# design.net
KiCad netlist of a schematic drawn in EasyEDA Pro
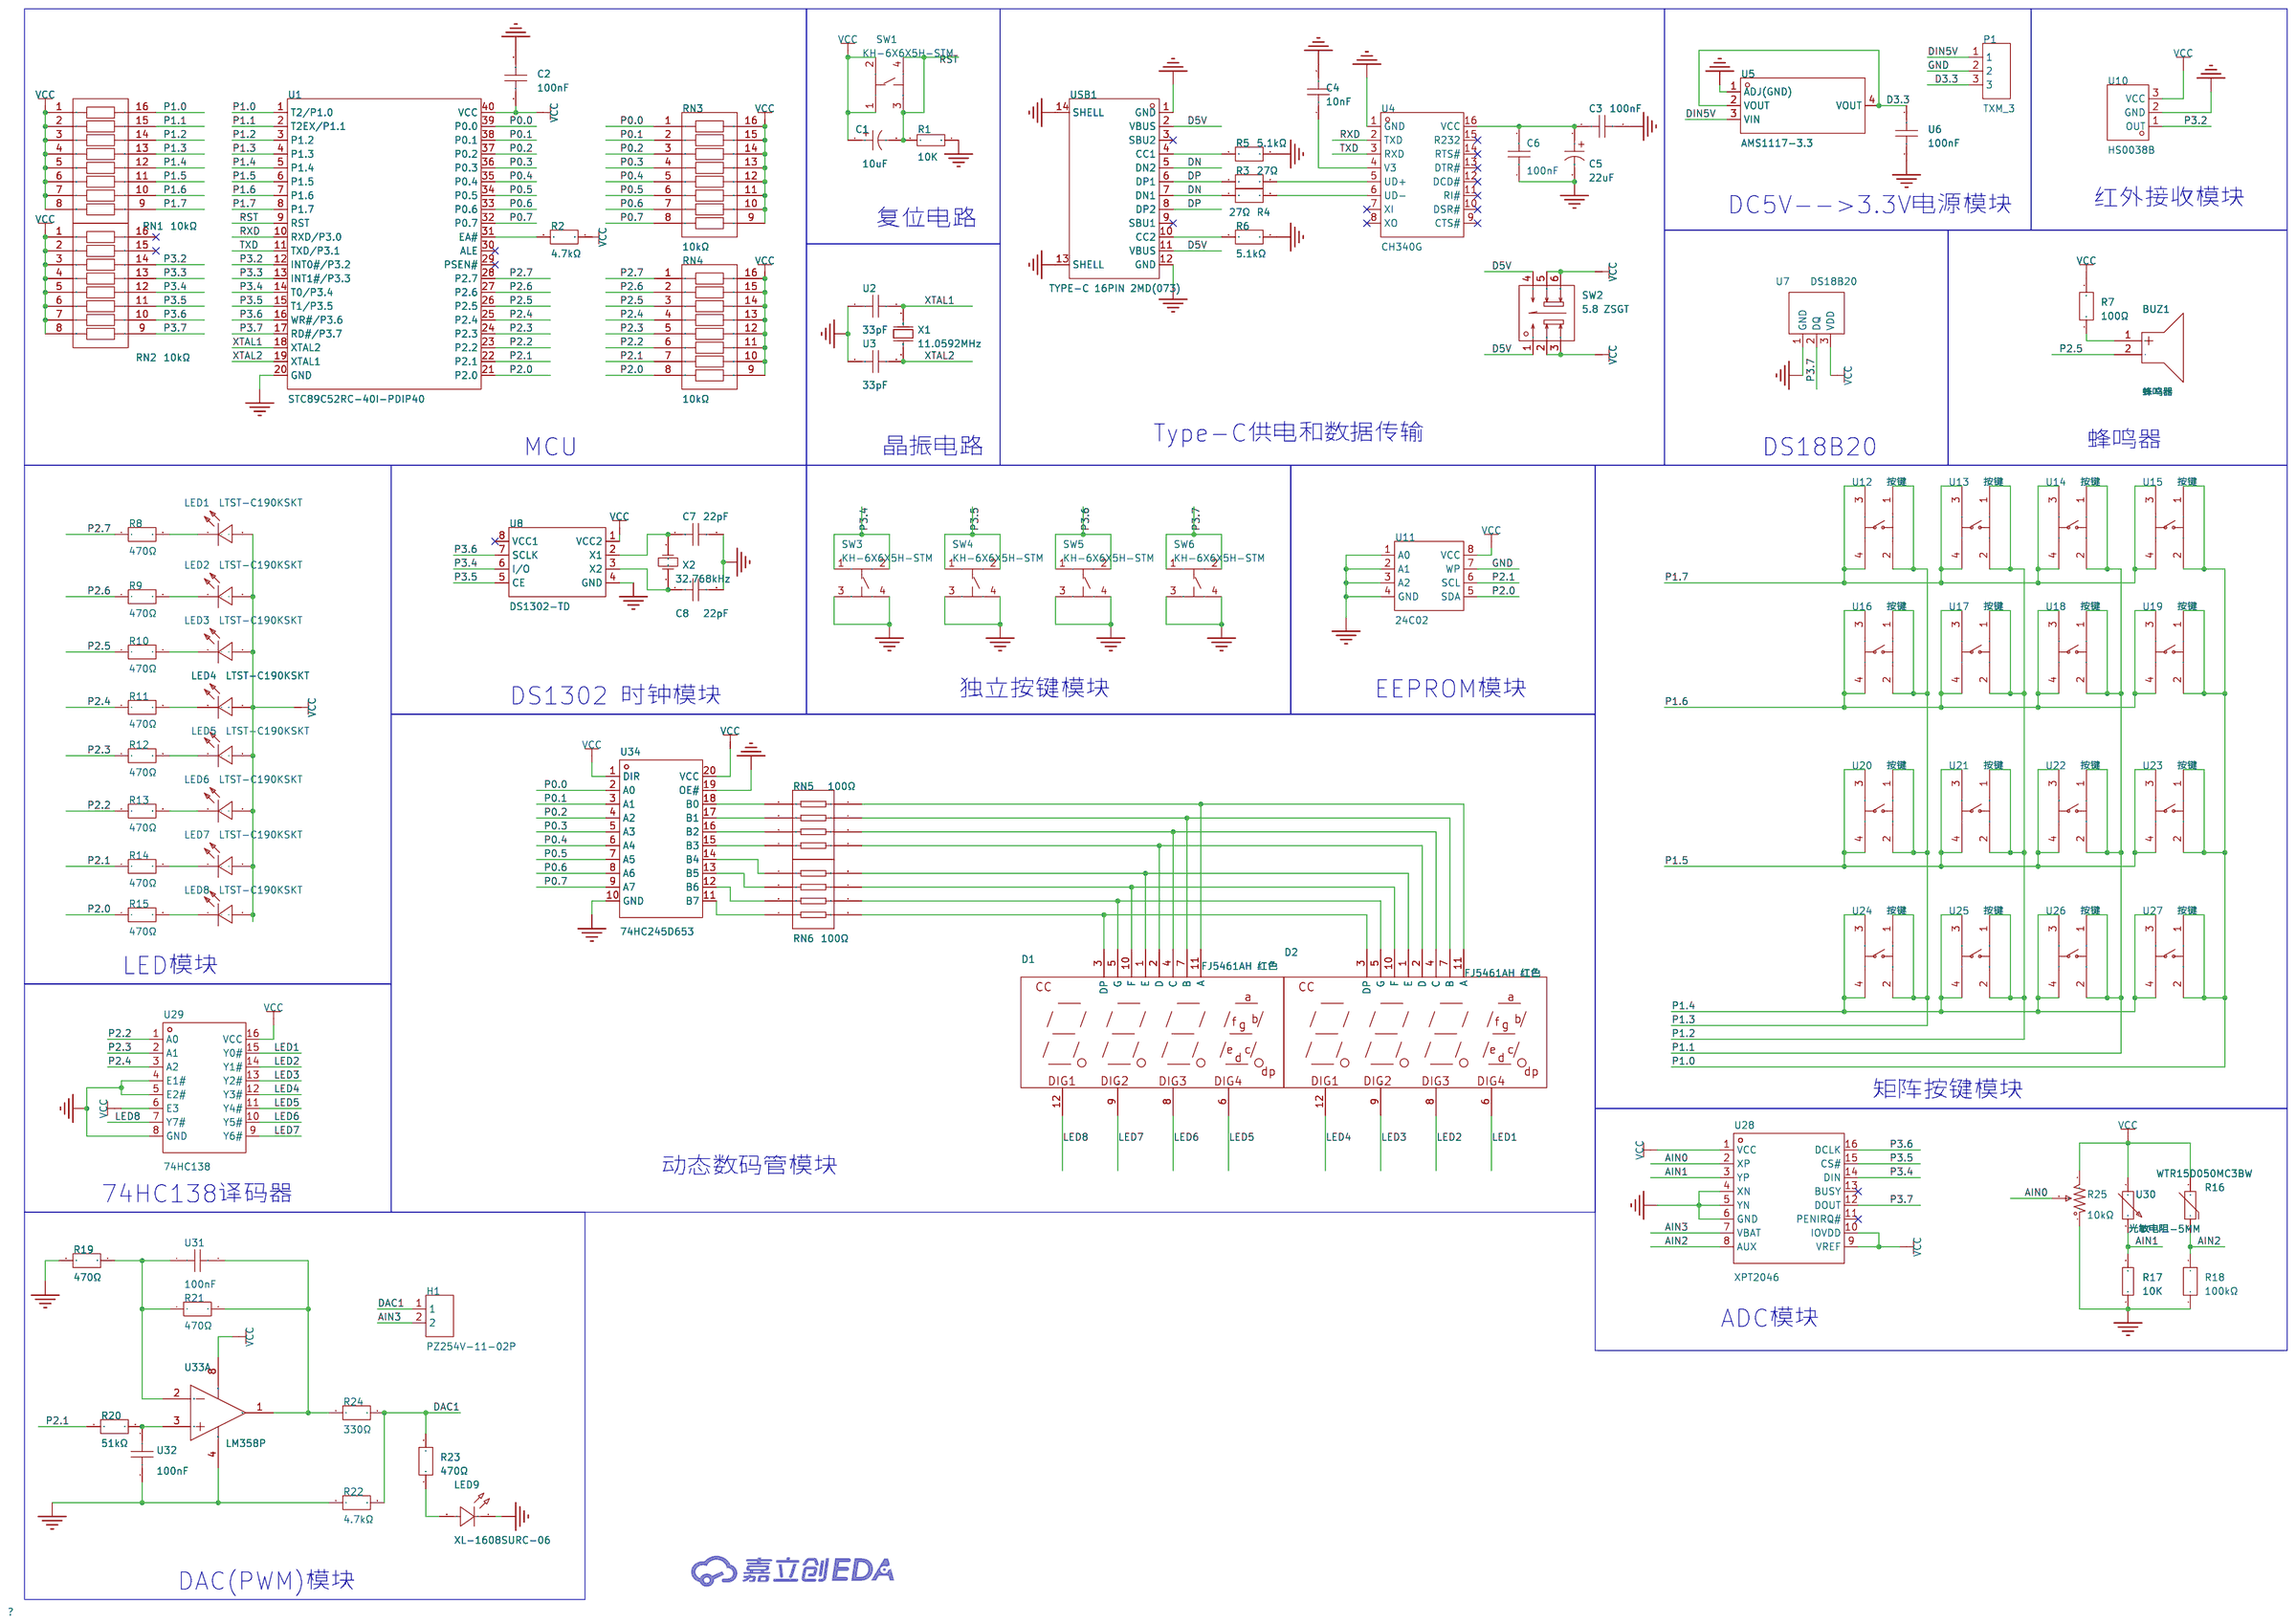
[diagram p0: schematic sheet]

(export (version "E")
  (design (tool "Eeschema 10.0.6"))
  (components
    (comp (ref "BUZ1")
      (value "蜂鸣器")
      (footprint "easyedapro:BUZ-TH_BD9.0-P5.00-D0.6-FD")
      (libsource (lib "easyedapro") (part "蜂鸣器"))
    )
    (comp (ref "C1")
      (value "10uF")
      (footprint "easyedapro:CAP-TH_BD10.0-P5.00-D0.6-FD_1")
      (description "容值:10uF;精度:±20%;额定电压:450V;纹波电流:200mA@100kHz;等效串联电阻(ESR):9Ω@100kHz;")
      (fields (field (name "Manufacturer Part") "CV100MPA16B") (field (name "Manufacturer") "TWBOR(伯鸿)"))
      (libsource (lib "easyedapro") (part "CV100MPA16B"))
    )
    (comp (ref "C2")
      (value "100nF")
      (footprint "easyedapro:C0603")
      (description "容值:100nF;精度:±10%;额定电压:25V;温度系数:X7R;")
      (fields
        (field (name "Manufacturer Part") "0603X7R104K250NT")
        (field (name "Manufacturer") "AIDE(爱迪电容)")
      )
      (libsource (lib "easyedapro") (part "0603X7R104K250NT"))
    )
    (comp (ref "C3")
      (value "100nF")
      (footprint "easyedapro:C0603")
      (description "容值:100nF;精度:±10%;额定电压:25V;温度系数:X7R;")
      (fields
        (field (name "Manufacturer Part") "0603X7R104K250NT")
        (field (name "Manufacturer") "AIDE(爱迪电容)")
      )
      (libsource (lib "easyedapro") (part "0603X7R104K250NT"))
    )
    (comp (ref "C4")
      (value "10nF")
      (footprint "easyedapro:C0603")
      (description "容值:10nF;精度:±10%;额定电压:200V;温度系数:X7R;")
      (fields
        (field (name "Manufacturer Part") "C0603X103K2RECAUTO")
        (field (name "Manufacturer") "KEMET(基美)")
      )
      (libsource (lib "easyedapro") (part "C0603X103K2RECAUTO"))
    )
    (comp (ref "C5")
      (value "22uF")
      (footprint "easyedapro:CAP-SMD_BD5.0-L5.3-W5.3-LS6.0-FD-H5.7")
      (description "容值:22uF;精度:±20%;额定电压:35V;纹波电流:95mA@120Hz;等效串联电阻(ESR):1.8Ω;")
      (fields (field (name "Manufacturer Part") "JVE35V22M5X6") (field (name "Manufacturer") "捷而瑞"))
      (libsource (lib "easyedapro") (part "JVE35V22M5X6"))
    )
    (comp (ref "C6")
      (value "100nF")
      (footprint "easyedapro:C0603")
      (description "容值:100nF;精度:±10%;额定电压:25V;温度系数:X7R;")
      (fields
        (field (name "Manufacturer Part") "0603X7R104K250NT")
        (field (name "Manufacturer") "AIDE(爱迪电容)")
      )
      (libsource (lib "easyedapro") (part "0603X7R104K250NT"))
    )
    (comp (ref "C7")
      (value "22pF")
      (footprint "easyedapro:C0603")
      (description "容值:22pF;精度:±10%;额定电压:16V;温度系数:C0G;")
      (fields
        (field (name "Manufacturer Part") "C0603C220K4GACAUTO")
        (field (name "Manufacturer") "KEMET(基美)")
      )
      (libsource (lib "easyedapro") (part "C0603C220K4GACAUTO"))
    )
    (comp (ref "C8")
      (value "22pF")
      (footprint "easyedapro:C0603")
      (description "容值:22pF;精度:±10%;额定电压:16V;温度系数:C0G;")
      (fields
        (field (name "Manufacturer Part") "C0603C220K4GACAUTO")
        (field (name "Manufacturer") "KEMET(基美)")
      )
      (libsource (lib "easyedapro") (part "C0603C220K4GACAUTO"))
    )
    (comp (ref "D1")
      (value "FJ5461AH 红色")
      (footprint "easyedapro:LED-SEG-TH_FJ5461AH")
      (description "数码管位数:4位;功耗:-;发光颜色:红色;LED极性:共阴极;数字/字母大小(英寸):0.56;")
      (fields (field (name "Manufacturer") "志浩"))
      (libsource (lib "easyedapro") (part "FJ5461AH red"))
    )
    (comp (ref "D2")
      (value "FJ5461AH 红色")
      (footprint "easyedapro:LED-SEG-TH_FJ5461AH")
      (description "数码管位数:4位;功耗:-;发光颜色:红色;LED极性:共阴极;数字/字母大小(英寸):0.56;")
      (fields (field (name "Manufacturer") "志浩"))
      (libsource (lib "easyedapro") (part "FJ5461AH red"))
    )
    (comp (ref "H1")
      (value "PZ254V-11-02P")
      (footprint "easyedapro:HDR-TH_2P-P2.54-V-M")
      (fields (field (name "Manufacturer") "XFCN(兴飞)"))
      (libsource (lib "easyedapro") (part "PZ254V-11-02P"))
    )
    (comp (ref "LED1")
      (value "LTST-C190KSKT")
      (footprint "easyedapro:LED0603-RD")
      (fields (field (name "Manufacturer") "LITEON(光宝)"))
      (libsource (lib "easyedapro") (part "LTST-C190KSKT"))
    )
    (comp (ref "LED2")
      (value "LTST-C190KSKT")
      (footprint "easyedapro:LED0603-RD")
      (fields (field (name "Manufacturer") "LITEON(光宝)"))
      (libsource (lib "easyedapro") (part "LTST-C190KSKT"))
    )
    (comp (ref "LED3")
      (value "LTST-C190KSKT")
      (footprint "easyedapro:LED0603-RD")
      (fields (field (name "Manufacturer") "LITEON(光宝)"))
      (libsource (lib "easyedapro") (part "LTST-C190KSKT"))
    )
    (comp (ref "LED4")
      (value "LTST-C190KSKT")
      (footprint "easyedapro:LED0603-RD")
      (fields (field (name "Manufacturer") "LITEON(光宝)"))
      (libsource (lib "easyedapro") (part "LTST-C190KSKT"))
    )
    (comp (ref "LED5")
      (value "LTST-C190KSKT")
      (footprint "easyedapro:LED0603-RD")
      (fields (field (name "Manufacturer") "LITEON(光宝)"))
      (libsource (lib "easyedapro") (part "LTST-C190KSKT"))
    )
    (comp (ref "LED6")
      (value "LTST-C190KSKT")
      (footprint "easyedapro:LED0603-RD")
      (fields (field (name "Manufacturer") "LITEON(光宝)"))
      (libsource (lib "easyedapro") (part "LTST-C190KSKT"))
    )
    (comp (ref "LED7")
      (value "LTST-C190KSKT")
      (footprint "easyedapro:LED0603-RD")
      (fields (field (name "Manufacturer") "LITEON(光宝)"))
      (libsource (lib "easyedapro") (part "LTST-C190KSKT"))
    )
    (comp (ref "LED8")
      (value "LTST-C190KSKT")
      (footprint "easyedapro:LED0603-RD")
      (fields (field (name "Manufacturer") "LITEON(光宝)"))
      (libsource (lib "easyedapro") (part "LTST-C190KSKT"))
    )
    (comp (ref "LED9")
      (value "XL-1608SURC-06")
      (footprint "easyedapro:LED0603-RD_RED")
      (fields (field (name "Manufacturer") "XINGLIGHT(成兴光)"))
      (libsource (lib "easyedapro") (part "XL-1608SURC-06"))
    )
    (comp (ref "P1")
      (value "TXM_3")
      (footprint "easyedapro:HDR-TH_3P-P2.54-V-M-A")
      (libsource (lib "easyedapro") (part "TXM_3"))
    )
    (comp (ref "R1") (value "10K") (footprint "easyedapro:R0603") (libsource (lib "easyedapro") (part "电阻")))
    (comp (ref "R2")
      (value "4.7kΩ")
      (footprint "easyedapro:R0805")
      (description "电阻类型:厚膜电阻;阻值:4.7kΩ;精度:±1%;功率:125mW;工作电压:-;温度系数:±100ppm/°C;")
      (fields
        (field (name "Manufacturer Part") "ERJ-U06F4701V")
        (field (name "Manufacturer") "PANASONIC(松下)")
      )
      (libsource (lib "easyedapro") (part "ERJ-U06F4701V"))
    )
    (comp (ref "R3")
      (value "27Ω")
      (footprint "easyedapro:R0805")
      (description "电阻类型:厚膜电阻;阻值:27Ω;精度:±5%;功率:125mW;工作电压:150V;温度系数:±100ppm/°C;")
      (fields (field (name "Manufacturer Part") "FRC0805J270 TS") (field (name "Manufacturer") "FOJAN(富捷)"))
      (libsource (lib "easyedapro") (part "FRC0805J270 TS"))
    )
    (comp (ref "R4")
      (value "27Ω")
      (footprint "easyedapro:R0805")
      (description "电阻类型:厚膜电阻;阻值:27Ω;精度:±5%;功率:125mW;工作电压:150V;温度系数:±100ppm/°C;")
      (fields (field (name "Manufacturer Part") "FRC0805J270 TS") (field (name "Manufacturer") "FOJAN(富捷)"))
      (libsource (lib "easyedapro") (part "FRC0805J270 TS"))
    )
    (comp (ref "R5")
      (value "5.1kΩ")
      (footprint "easyedapro:R0603")
      (description "电阻类型:薄膜电阻;阻值:5.1kΩ;精度:±0.01%;功率:100mW;温度系数:±2ppm/°C;")
      (fields
        (field (name "Manufacturer Part") "RNCF0603TKW5K10")
        (field (name "Manufacturer") "SEI(Stackpole Electronics Inc.)")
      )
      (libsource (lib "easyedapro") (part "RNCF0603TKW5K10"))
    )
    (comp (ref "R6")
      (value "5.1kΩ")
      (footprint "easyedapro:R0603")
      (description "电阻类型:薄膜电阻;阻值:5.1kΩ;精度:±0.01%;功率:100mW;温度系数:±2ppm/°C;")
      (fields
        (field (name "Manufacturer Part") "RNCF0603TKW5K10")
        (field (name "Manufacturer") "SEI(Stackpole Electronics Inc.)")
      )
      (libsource (lib "easyedapro") (part "RNCF0603TKW5K10"))
    )
    (comp (ref "R7")
      (value "100Ω")
      (footprint "easyedapro:R1206")
      (description "电阻类型:-;阻值:100Ω;精度:±5%;功率:250mW;工作电压:200V;")
      (fields
        (field (name "Manufacturer Part") "CQ06W4J0101T5E")
        (field (name "Manufacturer") "UNI-ROYAL(厚声)")
      )
      (libsource (lib "easyedapro") (part "CQ06W4J0101T5E"))
    )
    (comp (ref "R8")
      (value "470Ω")
      (footprint "easyedapro:R0402")
      (description "电阻类型:厚膜电阻;阻值:470Ω;精度:±1%;功率:62.5mW;工作电压:50V;温度系数:±100ppm/°C;")
      (fields (field (name "Manufacturer Part") "FRC0402F4700TS") (field (name "Manufacturer") "FOJAN(富捷)"))
      (libsource (lib "easyedapro") (part "FRC0402F4700TS"))
    )
    (comp (ref "R9")
      (value "470Ω")
      (footprint "easyedapro:R0402")
      (description "电阻类型:厚膜电阻;阻值:470Ω;精度:±1%;功率:62.5mW;工作电压:50V;温度系数:±100ppm/°C;")
      (fields (field (name "Manufacturer Part") "FRC0402F4700TS") (field (name "Manufacturer") "FOJAN(富捷)"))
      (libsource (lib "easyedapro") (part "FRC0402F4700TS"))
    )
    (comp (ref "R10")
      (value "470Ω")
      (footprint "easyedapro:R0402")
      (description "电阻类型:厚膜电阻;阻值:470Ω;精度:±1%;功率:62.5mW;工作电压:50V;温度系数:±100ppm/°C;")
      (fields (field (name "Manufacturer Part") "FRC0402F4700TS") (field (name "Manufacturer") "FOJAN(富捷)"))
      (libsource (lib "easyedapro") (part "FRC0402F4700TS"))
    )
    (comp (ref "R11")
      (value "470Ω")
      (footprint "easyedapro:R0402")
      (description "电阻类型:厚膜电阻;阻值:470Ω;精度:±1%;功率:62.5mW;工作电压:50V;温度系数:±100ppm/°C;")
      (fields (field (name "Manufacturer Part") "FRC0402F4700TS") (field (name "Manufacturer") "FOJAN(富捷)"))
      (libsource (lib "easyedapro") (part "FRC0402F4700TS"))
    )
    (comp (ref "R12")
      (value "470Ω")
      (footprint "easyedapro:R0402")
      (description "电阻类型:厚膜电阻;阻值:470Ω;精度:±1%;功率:62.5mW;工作电压:50V;温度系数:±100ppm/°C;")
      (fields (field (name "Manufacturer Part") "FRC0402F4700TS") (field (name "Manufacturer") "FOJAN(富捷)"))
      (libsource (lib "easyedapro") (part "FRC0402F4700TS"))
    )
    (comp (ref "R13")
      (value "470Ω")
      (footprint "easyedapro:R0402")
      (description "电阻类型:厚膜电阻;阻值:470Ω;精度:±1%;功率:62.5mW;工作电压:50V;温度系数:±100ppm/°C;")
      (fields (field (name "Manufacturer Part") "FRC0402F4700TS") (field (name "Manufacturer") "FOJAN(富捷)"))
      (libsource (lib "easyedapro") (part "FRC0402F4700TS"))
    )
    (comp (ref "R14")
      (value "470Ω")
      (footprint "easyedapro:R0402")
      (description "电阻类型:厚膜电阻;阻值:470Ω;精度:±1%;功率:62.5mW;工作电压:50V;温度系数:±100ppm/°C;")
      (fields (field (name "Manufacturer Part") "FRC0402F4700TS") (field (name "Manufacturer") "FOJAN(富捷)"))
      (libsource (lib "easyedapro") (part "FRC0402F4700TS"))
    )
    (comp (ref "R15")
      (value "470Ω")
      (footprint "easyedapro:R0402")
      (description "电阻类型:厚膜电阻;阻值:470Ω;精度:±1%;功率:62.5mW;工作电压:50V;温度系数:±100ppm/°C;")
      (fields (field (name "Manufacturer Part") "FRC0402F4700TS") (field (name "Manufacturer") "FOJAN(富捷)"))
      (libsource (lib "easyedapro") (part "FRC0402F4700TS"))
    )
    (comp (ref "R16")
      (value "WTR15D050MC3BW")
      (footprint "easyedapro:RES-TH_L17.5-W6.0-P7.50-D0.8-S5.20")
      (description "阻值(25°C):-;电阻精度:-;最大工作电压:-;功率:-;")
      (fields (field (name "Manufacturer") "WMEC(万明)"))
      (libsource (lib "easyedapro") (part "WTR15D050MC3BW"))
    )
    (comp (ref "R17") (value "10K") (footprint "easyedapro:R0603") (libsource (lib "easyedapro") (part "电阻")))
    (comp (ref "R18")
      (value "100kΩ")
      (footprint "easyedapro:R1206")
      (description "阻值:100kΩ;精度:±0.5%;")
      (fields (field (name "Manufacturer Part") "WF12R1003DTL") (field (name "Manufacturer") "Walsin(华新科)"))
      (libsource (lib "easyedapro") (part "WF12R1003DTL"))
    )
    (comp (ref "R19")
      (value "470Ω")
      (footprint "easyedapro:R0402")
      (description "电阻类型:厚膜电阻;阻值:470Ω;精度:±1%;功率:62.5mW;工作电压:50V;温度系数:±100ppm/°C;")
      (fields (field (name "Manufacturer Part") "FRC0402F4700TS") (field (name "Manufacturer") "FOJAN(富捷)"))
      (libsource (lib "easyedapro") (part "FRC0402F4700TS"))
    )
    (comp (ref "R20")
      (value "51kΩ")
      (footprint "easyedapro:R1812")
      (description "电阻类型:厚膜电阻;阻值:51kΩ;精度:±5%;功率:750mW;工作电压:200V;温度系数:±100ppm/°C;")
      (fields (field (name "Manufacturer Part") "FRC1812J513 TS") (field (name "Manufacturer") "FOJAN(富捷)"))
      (libsource (lib "easyedapro") (part "FRC1812J513 TS"))
    )
    (comp (ref "R21")
      (value "470Ω")
      (footprint "easyedapro:R0402")
      (description "电阻类型:厚膜电阻;阻值:470Ω;精度:±1%;功率:62.5mW;工作电压:50V;温度系数:±100ppm/°C;")
      (fields (field (name "Manufacturer Part") "FRC0402F4700TS") (field (name "Manufacturer") "FOJAN(富捷)"))
      (libsource (lib "easyedapro") (part "FRC0402F4700TS"))
    )
    (comp (ref "R22")
      (value "4.7kΩ")
      (footprint "easyedapro:R0603")
      (description "阻值:4.7kΩ;精度:±1%;功率:100mW;")
      (fields (field (name "Manufacturer Part") "RCA034K7FLF") (field (name "Manufacturer") "HKR(香港电阻)"))
      (libsource (lib "easyedapro") (part "RCA034K7FLF"))
    )
    (comp (ref "R23")
      (value "470Ω")
      (footprint "easyedapro:R0402")
      (description "电阻类型:厚膜电阻;阻值:470Ω;精度:±1%;功率:62.5mW;工作电压:50V;温度系数:±100ppm/°C;")
      (fields (field (name "Manufacturer Part") "FRC0402F4700TS") (field (name "Manufacturer") "FOJAN(富捷)"))
      (libsource (lib "easyedapro") (part "FRC0402F4700TS"))
    )
    (comp (ref "R24")
      (value "330Ω")
      (footprint "easyedapro:R2010")
      (description "电阻类型:厚膜电阻;阻值:330Ω;精度:±5%;功率:750mW;温度系数:±100ppm/°C;")
      (fields (field (name "Manufacturer Part") "AC2010JK-07330RL") (field (name "Manufacturer") "YAGEO(国巨)"))
      (libsource (lib "easyedapro") (part "AC2010JK-07330RL"))
    )
    (comp (ref "R25")
      (value "10kΩ")
      (footprint "easyedapro:RES-ADJ-SMD_RM065-V1")
      (description "阻值:10kΩ;精度:±25%;功率:100mW;")
      (fields (field (name "Manufacturer Part") "RM065-103(10K)") (field (name "Manufacturer") "BOCHEN(博晨)"))
      (libsource (lib "easyedapro") (part "RM065-103(10K)"))
    )
    (comp (ref "RN1")
      (value "10kΩ")
      (footprint "easyedapro:DIP-16_L22.0-W6.7-P2.54-LS7.6-BL")
      (description "电阻器数:8;阻值:10kΩ;精度:±2%;单个元件功率:250mW;温度系数:±100ppm/°C;")
      (fields (field (name "Manufacturer Part") "4116R-1-103LF") (field (name "Manufacturer") "BOURNS"))
      (libsource (lib "easyedapro") (part "4116R-1-103LF"))
    )
    (comp (ref "RN2")
      (value "10kΩ")
      (footprint "easyedapro:DIP-16_L22.0-W6.7-P2.54-LS7.6-BL")
      (description "电阻器数:8;阻值:10kΩ;精度:±2%;单个元件功率:250mW;温度系数:±100ppm/°C;")
      (fields (field (name "Manufacturer Part") "4116R-1-103LF") (field (name "Manufacturer") "BOURNS"))
      (libsource (lib "easyedapro") (part "4116R-1-103LF"))
    )
    (comp (ref "RN3")
      (value "10kΩ")
      (footprint "easyedapro:DIP-16_L22.0-W6.7-P2.54-LS7.6-BL")
      (description "电阻器数:8;阻值:10kΩ;精度:±2%;单个元件功率:250mW;温度系数:±100ppm/°C;")
      (fields (field (name "Manufacturer Part") "4116R-1-103LF") (field (name "Manufacturer") "BOURNS"))
      (libsource (lib "easyedapro") (part "4116R-1-103LF"))
    )
    (comp (ref "RN4")
      (value "10kΩ")
      (footprint "easyedapro:DIP-16_L22.0-W6.7-P2.54-LS7.6-BL")
      (description "电阻器数:8;阻值:10kΩ;精度:±2%;单个元件功率:250mW;温度系数:±100ppm/°C;")
      (fields (field (name "Manufacturer Part") "4116R-1-103LF") (field (name "Manufacturer") "BOURNS"))
      (libsource (lib "easyedapro") (part "4116R-1-103LF"))
    )
    (comp (ref "RN5")
      (value "100Ω")
      (footprint "easyedapro:RES-ARRAY-SMD_0402-8P-L2.0-W1.0-BL")
      (description "电阻器数:4;阻值:100Ω;精度:±5%;单个元件功率:62.5mW;温度系数:±200ppm/°C;")
      (fields
        (field (name "Manufacturer Part") "4D02WGJ0101TCE")
        (field (name "Manufacturer") "UNI-ROYAL(厚声)")
      )
      (libsource (lib "easyedapro") (part "4D02WGJ0101TCE"))
    )
    (comp (ref "RN6")
      (value "100Ω")
      (footprint "easyedapro:RES-ARRAY-SMD_0402-8P-L2.0-W1.0-BL")
      (description "电阻器数:4;阻值:100Ω;精度:±5%;单个元件功率:62.5mW;温度系数:±200ppm/°C;")
      (fields
        (field (name "Manufacturer Part") "4D02WGJ0101TCE")
        (field (name "Manufacturer") "UNI-ROYAL(厚声)")
      )
      (libsource (lib "easyedapro") (part "4D02WGJ0101TCE"))
    )
    (comp (ref "SW1")
      (value "KH-6X6X5H-STM")
      (footprint "easyedapro:SW-SMD_4P-L6.0-W6.0-P4.50-LS9.0_H5.0")
      (description "电路结构:单刀单掷;按钮形状:圆形按钮;安装方式:立贴;开关长度:6mm;开关宽度:6mm;开关高度:5mm;带支架:不带;触点电流:50mA;额定电压(DC):12V;机械寿命:8万次;")
      (fields (field (name "Manufacturer") "kinghelm(金航标)"))
      (libsource (lib "easyedapro") (part "KH-6X6X5H-STM"))
    )
    (comp (ref "SW2")
      (value "5.8 ZSGT")
      (footprint "easyedapro:SW-TH_5.8ZSGT")
      (description "电路结构:双刀双掷;自锁/无锁:自锁;安装方式:直插;触点电流:110mA;额定电压 (DC):30V;带灯:不带;作用力:1.5N;机械寿命:10万次;")
      (fields (field (name "Manufacturer") "SHOU HAN(首韩)"))
      (libsource (lib "easyedapro") (part "5.8 ZSGT"))
    )
    (comp (ref "SW3")
      (value "KH-6X6X5H-STM")
      (footprint "easyedapro:SW-SMD_4P-L6.0-W6.0-P4.50-LS9.0_H5.0")
      (description "电路结构:单刀单掷;按钮形状:圆形按钮;安装方式:立贴;开关长度:6mm;开关宽度:6mm;开关高度:5mm;带支架:不带;触点电流:50mA;额定电压(DC):12V;机械寿命:8万次;")
      (fields (field (name "Manufacturer") "kinghelm(金航标)"))
      (libsource (lib "easyedapro") (part "KH-6X6X5H-STM"))
    )
    (comp (ref "SW4")
      (value "KH-6X6X5H-STM")
      (footprint "easyedapro:SW-SMD_4P-L6.0-W6.0-P4.50-LS9.0_H5.0")
      (description "电路结构:单刀单掷;按钮形状:圆形按钮;安装方式:立贴;开关长度:6mm;开关宽度:6mm;开关高度:5mm;带支架:不带;触点电流:50mA;额定电压(DC):12V;机械寿命:8万次;")
      (fields (field (name "Manufacturer") "kinghelm(金航标)"))
      (libsource (lib "easyedapro") (part "KH-6X6X5H-STM"))
    )
    (comp (ref "SW5")
      (value "KH-6X6X5H-STM")
      (footprint "easyedapro:SW-SMD_4P-L6.0-W6.0-P4.50-LS9.0_H5.0")
      (description "电路结构:单刀单掷;按钮形状:圆形按钮;安装方式:立贴;开关长度:6mm;开关宽度:6mm;开关高度:5mm;带支架:不带;触点电流:50mA;额定电压(DC):12V;机械寿命:8万次;")
      (fields (field (name "Manufacturer") "kinghelm(金航标)"))
      (libsource (lib "easyedapro") (part "KH-6X6X5H-STM"))
    )
    (comp (ref "SW6")
      (value "KH-6X6X5H-STM")
      (footprint "easyedapro:SW-SMD_4P-L6.0-W6.0-P4.50-LS9.0_H5.0")
      (description "电路结构:单刀单掷;按钮形状:圆形按钮;安装方式:立贴;开关长度:6mm;开关宽度:6mm;开关高度:5mm;带支架:不带;触点电流:50mA;额定电压(DC):12V;机械寿命:8万次;")
      (fields (field (name "Manufacturer") "kinghelm(金航标)"))
      (libsource (lib "easyedapro") (part "KH-6X6X5H-STM"))
    )
    (comp (ref "U1")
      (value "STC89C52RC-40I-PDIP40")
      (footprint "easyedapro:DIP-40_L52.0-W13.7-P2.54-LS15.2-BL")
      (description "CPU内核:51系列;应用领域:-;")
      (fields (field (name "Manufacturer") "STC"))
      (libsource (lib "easyedapro") (part "STC89C52RC-40I"))
    )
    (comp (ref "U2")
      (value "33pF")
      (footprint "easyedapro:C0603")
      (description "容值:33pF;精度:±1%;额定电压:50V;温度系数:-;")
      (fields
        (field (name "Manufacturer Part") "GRM1885C1H330FA01D")
        (field (name "Manufacturer") "muRata(村田)")
      )
      (libsource (lib "easyedapro") (part "GRM1885C1H330FA01D"))
    )
    (comp (ref "U3")
      (value "33pF")
      (footprint "easyedapro:C0603")
      (description "容值:33pF;精度:±1%;额定电压:50V;温度系数:-;")
      (fields
        (field (name "Manufacturer Part") "GRM1885C1H330FA01D")
        (field (name "Manufacturer") "muRata(村田)")
      )
      (libsource (lib "easyedapro") (part "GRM1885C1H330FA01D"))
    )
    (comp (ref "U4")
      (value "CH340G")
      (footprint "easyedapro:SOIC-16_L9.9-W3.9-P1.27-LS6.0-BL")
      (description "应用功能:USB转UART;接口协议:USB 2.0;数据速率:2Mbps;")
      (fields (field (name "Manufacturer") "WCH(南京沁恒)"))
      (libsource (lib "easyedapro") (part "CH340G"))
    )
    (comp (ref "U5")
      (value "AMS1117-3.3")
      (footprint "easyedapro:SOT-223-3_L6.5-W3.4-P2.30-LS7.0-BR")
      (description "输出类型:固定;最大输入电压:18V;输出电压:3.3V;最大输出电流:1A;电源纹波抑制比(PSRR):60dB@(120Hz);输出极性:正极;")
      (fields (field (name "Manufacturer") "YONGYUTAI(永裕泰)"))
      (libsource (lib "easyedapro") (part "AMS1117-3.3_C2891839"))
    )
    (comp (ref "U6")
      (value "100nF")
      (footprint "easyedapro:C0603")
      (description "容值:100nF;精度:±5%;额定电压:16V;温度系数:-;")
      (fields
        (field (name "Manufacturer Part") "0603Y0160104JDR")
        (field (name "Manufacturer") "Knowles(楼氏)")
      )
      (libsource (lib "easyedapro") (part "0603Y0160104JDR"))
    )
    (comp (ref "U7")
      (value "DS18B20")
      (footprint "easyedapro:TO-92-3_L4.6-W3.6-P1.27-L-1")
      (description "温度范围:-55°C~+125°C;精度:±0.5°C;接口类型:单总线;")
      (fields (field (name "Manufacturer") "Mysentech(敏源传感)"))
      (libsource (lib "easyedapro") (part "DS18B20_C20611523"))
    )
    (comp (ref "U8")
      (value "DS1302-TD")
      (footprint "easyedapro:SOP-8_L4.9-W3.9-P1.27-LS6.0-BL")
      (fields (field (name "Manufacturer") "TDSEMIC(拓电半导体)"))
      (libsource (lib "easyedapro") (part "DS1302-TD"))
    )
    (comp (ref "U10")
      (value "HS0038B")
      (footprint "easyedapro:OPTO-TH_HS0038B-A")
      (libsource (lib "easyedapro") (part "HS0038B_C9900004117"))
    )
    (comp (ref "U11")
      (value "24C02")
      (footprint "easyedapro:SOP-8_L4.9-W3.9-P1.27-LS6.0-BL")
      (description "24C02是电可擦除PROM，采用256x8-bit的组织架构，具有页写能力，每页为8字节。支持I2C总线传输协议，工作电压范围1.8V~5.5V，擦写寿命100万次，数据保持时间100年。")
      (fields (field (name "Manufacturer") "HX(恒佳兴)"))
      (libsource (lib "easyedapro") (part "24C02"))
    )
    (comp (ref "U12")
      (value "按键")
      (footprint "easyedapro:SW-SMD_4P-L6.0-W6.0-P4.50-LS9.0-2")
      (libsource (lib "easyedapro") (part "SW"))
    )
    (comp (ref "U13")
      (value "按键")
      (footprint "easyedapro:SW-SMD_4P-L6.0-W6.0-P4.50-LS9.0-2")
      (libsource (lib "easyedapro") (part "SW"))
    )
    (comp (ref "U14")
      (value "按键")
      (footprint "easyedapro:SW-SMD_4P-L6.0-W6.0-P4.50-LS9.0-2")
      (libsource (lib "easyedapro") (part "SW"))
    )
    (comp (ref "U15")
      (value "按键")
      (footprint "easyedapro:SW-SMD_4P-L6.0-W6.0-P4.50-LS9.0-2")
      (libsource (lib "easyedapro") (part "SW"))
    )
    (comp (ref "U16")
      (value "按键")
      (footprint "easyedapro:SW-SMD_4P-L6.0-W6.0-P4.50-LS9.0-2")
      (libsource (lib "easyedapro") (part "SW"))
    )
    (comp (ref "U17")
      (value "按键")
      (footprint "easyedapro:SW-SMD_4P-L6.0-W6.0-P4.50-LS9.0-2")
      (libsource (lib "easyedapro") (part "SW"))
    )
    (comp (ref "U18")
      (value "按键")
      (footprint "easyedapro:SW-SMD_4P-L6.0-W6.0-P4.50-LS9.0-2")
      (libsource (lib "easyedapro") (part "SW"))
    )
    (comp (ref "U19")
      (value "按键")
      (footprint "easyedapro:SW-SMD_4P-L6.0-W6.0-P4.50-LS9.0-2")
      (libsource (lib "easyedapro") (part "SW"))
    )
    (comp (ref "U20")
      (value "按键")
      (footprint "easyedapro:SW-SMD_4P-L6.0-W6.0-P4.50-LS9.0-2")
      (libsource (lib "easyedapro") (part "SW"))
    )
    (comp (ref "U21")
      (value "按键")
      (footprint "easyedapro:SW-SMD_4P-L6.0-W6.0-P4.50-LS9.0-2")
      (libsource (lib "easyedapro") (part "SW"))
    )
    (comp (ref "U22")
      (value "按键")
      (footprint "easyedapro:SW-SMD_4P-L6.0-W6.0-P4.50-LS9.0-2")
      (libsource (lib "easyedapro") (part "SW"))
    )
    (comp (ref "U23")
      (value "按键")
      (footprint "easyedapro:SW-SMD_4P-L6.0-W6.0-P4.50-LS9.0-2")
      (libsource (lib "easyedapro") (part "SW"))
    )
    (comp (ref "U24")
      (value "按键")
      (footprint "easyedapro:SW-SMD_4P-L6.0-W6.0-P4.50-LS9.0-2")
      (libsource (lib "easyedapro") (part "SW"))
    )
    (comp (ref "U25")
      (value "按键")
      (footprint "easyedapro:SW-SMD_4P-L6.0-W6.0-P4.50-LS9.0-2")
      (libsource (lib "easyedapro") (part "SW"))
    )
    (comp (ref "U26")
      (value "按键")
      (footprint "easyedapro:SW-SMD_4P-L6.0-W6.0-P4.50-LS9.0-2")
      (libsource (lib "easyedapro") (part "SW"))
    )
    (comp (ref "U27")
      (value "按键")
      (footprint "easyedapro:SW-SMD_4P-L6.0-W6.0-P4.50-LS9.0-2")
      (libsource (lib "easyedapro") (part "SW"))
    )
    (comp (ref "U28")
      (value "XPT2046")
      (footprint "easyedapro:TSSOP-16_L5.0-W4.4-P0.65-LS6.4-BL")
      (description "接口类型:-;")
      (fields (field (name "Manufacturer") "XPT(矽普特)"))
      (libsource (lib "easyedapro") (part "XPT2046"))
    )
    (comp (ref "U29")
      (value "74HC138")
      (footprint "easyedapro:SOIC-16_L9.9-W3.9-P1.27-LS6.0-BL")
      (description "三八译码器，74系列逻辑芯片,2.0V-6.0V供电电压。")
      (fields (field (name "Manufacturer") "FM(富满)"))
      (libsource (lib "easyedapro") (part "74HC138"))
    )
    (comp (ref "U30")
      (value "光敏电阻-5MM")
      (footprint "easyedapro:RES-TH_L4.9-W4.3-P3.4")
      (libsource (lib "easyedapro") (part "光敏电阻-5MM"))
    )
    (comp (ref "U31")
      (value "100nF")
      (footprint "easyedapro:C0603")
      (description "容值:100nF;精度:±5%;额定电压:16V;温度系数:-;")
      (fields
        (field (name "Manufacturer Part") "0603Y0160104JDR")
        (field (name "Manufacturer") "Knowles(楼氏)")
      )
      (libsource (lib "easyedapro") (part "0603Y0160104JDR"))
    )
    (comp (ref "U32")
      (value "100nF")
      (footprint "easyedapro:C0603")
      (description "容值:100nF;精度:±5%;额定电压:16V;温度系数:-;")
      (fields
        (field (name "Manufacturer Part") "0603Y0160104JDR")
        (field (name "Manufacturer") "Knowles(楼氏)")
      )
      (libsource (lib "easyedapro") (part "0603Y0160104JDR"))
    )
    (comp (ref "U33")
      (value "LM358P")
      (footprint "easyedapro:DIP-8_L9.7-W6.4-P2.54-LS7.6-BL")
      (description "放大器数:双路;轨到轨:-;增益带宽积(GBP):1MHz;输入失调电压(Vos):2mV;压摆率(SR):-;输入偏置电流(Ib):45nA;")
      (fields (field (name "Manufacturer") "Slkor(萨科微)"))
      (libsource (lib "easyedapro") (part "LM358P_C5330384"))
    )
    (comp (ref "U34")
      (value "74HC245D653")
      (footprint "easyedapro:SOIC-20_L13.0-W7.6-P1.27-LS10.3-BL")
      (libsource (lib "easyedapro") (part "74HC245D653"))
    )
    (comp (ref "USB1")
      (value "TYPE-C 16PIN 2MD(073)")
      (footprint "easyedapro:USB-C-SMD_TYPE-C-6PIN-2MD-073")
      (description "连接器类型:Type-C;协议标准:USB 3.1;公母:母;安装方式:卧贴;触点数量:16P;端口数量:1;额定电流 - 电源:3A;工作温度:-25°C~+85°C;")
      (fields (field (name "Manufacturer") "SHOU HAN(首韩)"))
      (libsource (lib "easyedapro") (part "TYPE-C 16PIN 2MD(073)"))
    )
    (comp (ref "X1")
      (value "11.0592MHz")
      (footprint "easyedapro:HC-49US_L11.5-W4.5-P4.88")
      (description "晶振类型:直插晶振;频率:11.0592MHz;常温频差:±20ppm;负载电容:20pF;频率稳定度:±30ppm;")
      (fields
        (field (name "Manufacturer Part") "X49SD110592MSD2SC")
        (field (name "Manufacturer") "YXC(扬兴晶振)")
      )
      (libsource (lib "easyedapro") (part "X49SD110592MSD2SC"))
    )
    (comp (ref "X2")
      (value "32.768kHz")
      (footprint "easyedapro:OSC-TH_BD3.1-P0.8-D0.3")
      (description "晶振类型:直插晶振;频率:32.768kHz;常温频差:±10ppm;负载电容:12.5pF;频率稳定度:±20ppm;")
      (fields (field (name "Manufacturer Part") "X308032768KGB2SC") (field (name "Manufacturer") "YXC(扬兴晶振)"))
      (libsource (lib "easyedapro") (part "X308032768KGB2SC"))
    )
  )
  (nets
    (net (code "1") (name "/AIN0") (class "Default")
      (node (ref "R25") (pin "2") (pinfunction "2_2") (pintype "unspecified"))
      (node (ref "U28") (pin "2") (pinfunction "XP_2") (pintype "unspecified"))
    )
    (net (code "2") (name "/AIN1") (class "Default")
      (node (ref "R17") (pin "2") (pinfunction "2_2") (pintype "input"))
      (node (ref "U28") (pin "3") (pinfunction "YP_3") (pintype "unspecified"))
      (node (ref "U30") (pin "2") (pinfunction "2_2") (pintype "unspecified"))
    )
    (net (code "3") (name "/AIN2") (class "Default")
      (node (ref "R16") (pin "1") (pinfunction "1_1") (pintype "input"))
      (node (ref "R18") (pin "2") (pinfunction "2_2") (pintype "unspecified"))
      (node (ref "U28") (pin "8") (pinfunction "AUX_8") (pintype "unspecified"))
    )
    (net (code "4") (name "/AIN3") (class "Default")
      (node (ref "H1") (pin "2") (pinfunction "2_2") (pintype "unspecified"))
      (node (ref "U28") (pin "7") (pinfunction "VBAT_7") (pintype "unspecified"))
    )
    (net (code "5") (name "/D3.3") (class "Default")
      (node (ref "P1") (pin "3") (pinfunction "3_3") (pintype "unspecified"))
      (node (ref "U5") (pin "2") (pinfunction "VOUT_2") (pintype "unspecified"))
      (node (ref "U5") (pin "4") (pinfunction "VOUT_4") (pintype "unspecified"))
      (node (ref "U6") (pin "2") (pinfunction "2_2") (pintype "unspecified"))
    )
    (net (code "6") (name "/D5V") (class "Default")
      (node (ref "SW2") (pin "1") (pinfunction "1_1") (pintype "unspecified"))
      (node (ref "SW2") (pin "4") (pinfunction "4_4") (pintype "unspecified"))
      (node (ref "USB1") (pin "11") (pinfunction "VBUS_11") (pintype "unspecified"))
      (node (ref "USB1") (pin "2") (pinfunction "VBUS_2") (pintype "unspecified"))
    )
    (net (code "7") (name "/DAC1") (class "Default")
      (node (ref "H1") (pin "1") (pinfunction "1_1") (pintype "unspecified"))
      (node (ref "R22") (pin "2") (pinfunction "2_2") (pintype "unspecified"))
      (node (ref "R23") (pin "2") (pinfunction "2_2") (pintype "unspecified"))
      (node (ref "R24") (pin "2") (pinfunction "2_2") (pintype "unspecified"))
    )
    (net (code "8") (name "/DIN5V") (class "Default")
      (node (ref "P1") (pin "1") (pinfunction "1_1") (pintype "unspecified"))
      (node (ref "U5") (pin "3") (pinfunction "VIN_3") (pintype "unspecified"))
    )
    (net (code "9") (name "/DN") (class "Default")
      (node (ref "R4") (pin "1") (pinfunction "1_1") (pintype "unspecified"))
      (node (ref "USB1") (pin "5") (pinfunction "DN2_5") (pintype "unspecified"))
      (node (ref "USB1") (pin "7") (pinfunction "DN1_7") (pintype "unspecified"))
    )
    (net (code "10") (name "/DP") (class "Default")
      (node (ref "R3") (pin "1") (pinfunction "1_1") (pintype "unspecified"))
      (node (ref "USB1") (pin "6") (pinfunction "DP1_6") (pintype "unspecified"))
      (node (ref "USB1") (pin "8") (pinfunction "DP2_8") (pintype "unspecified"))
    )
    (net (code "11") (name "/LED1") (class "Default")
      (node (ref "D2") (pin "6") (pinfunction "DIG4_6") (pintype "input"))
      (node (ref "U29") (pin "15") (pinfunction "Y0#_15") (pintype "unspecified"))
    )
    (net (code "12") (name "/LED2") (class "Default")
      (node (ref "D2") (pin "8") (pinfunction "DIG3_8") (pintype "input"))
      (node (ref "U29") (pin "14") (pinfunction "Y1#_14") (pintype "unspecified"))
    )
    (net (code "13") (name "/LED3") (class "Default")
      (node (ref "D2") (pin "9") (pinfunction "DIG2_9") (pintype "input"))
      (node (ref "U29") (pin "13") (pinfunction "Y2#_13") (pintype "unspecified"))
    )
    (net (code "14") (name "/LED4") (class "Default")
      (node (ref "D2") (pin "12") (pinfunction "DIG1_12") (pintype "input"))
      (node (ref "U29") (pin "12") (pinfunction "Y3#_12") (pintype "unspecified"))
    )
    (net (code "15") (name "/LED5") (class "Default")
      (node (ref "D1") (pin "6") (pinfunction "DIG4_6") (pintype "input"))
      (node (ref "U29") (pin "11") (pinfunction "Y4#_11") (pintype "unspecified"))
    )
    (net (code "16") (name "/LED6") (class "Default")
      (node (ref "D1") (pin "8") (pinfunction "DIG3_8") (pintype "input"))
      (node (ref "U29") (pin "10") (pinfunction "Y5#_10") (pintype "unspecified"))
    )
    (net (code "17") (name "/LED7") (class "Default")
      (node (ref "D1") (pin "9") (pinfunction "DIG2_9") (pintype "input"))
      (node (ref "U29") (pin "9") (pinfunction "Y6#_9") (pintype "unspecified"))
    )
    (net (code "18") (name "/LED8") (class "Default")
      (node (ref "D1") (pin "12") (pinfunction "DIG1_12") (pintype "input"))
      (node (ref "U29") (pin "7") (pinfunction "Y7#_7") (pintype "unspecified"))
    )
    (net (code "19") (name "/P0.0") (class "Default")
      (node (ref "RN3") (pin "1") (pinfunction "1_1") (pintype "unspecified"))
      (node (ref "U1") (pin "39") (pinfunction "P0.0_39") (pintype "unspecified"))
      (node (ref "U34") (pin "2") (pinfunction "A0_2") (pintype "unspecified"))
    )
    (net (code "20") (name "/P0.1") (class "Default")
      (node (ref "RN3") (pin "2") (pinfunction "2_2") (pintype "unspecified"))
      (node (ref "U1") (pin "38") (pinfunction "P0.1_38") (pintype "unspecified"))
      (node (ref "U34") (pin "3") (pinfunction "A1_3") (pintype "unspecified"))
    )
    (net (code "21") (name "/P0.2") (class "Default")
      (node (ref "RN3") (pin "3") (pinfunction "3_3") (pintype "unspecified"))
      (node (ref "U1") (pin "37") (pinfunction "P0.2_37") (pintype "unspecified"))
      (node (ref "U34") (pin "4") (pinfunction "A2_4") (pintype "unspecified"))
    )
    (net (code "22") (name "/P0.3") (class "Default")
      (node (ref "RN3") (pin "4") (pinfunction "4_4") (pintype "unspecified"))
      (node (ref "U1") (pin "36") (pinfunction "P0.3_36") (pintype "unspecified"))
      (node (ref "U34") (pin "5") (pinfunction "A3_5") (pintype "unspecified"))
    )
    (net (code "23") (name "/P0.4") (class "Default")
      (node (ref "RN3") (pin "5") (pinfunction "5_5") (pintype "unspecified"))
      (node (ref "U1") (pin "35") (pinfunction "P0.4_35") (pintype "unspecified"))
      (node (ref "U34") (pin "6") (pinfunction "A4_6") (pintype "unspecified"))
    )
    (net (code "24") (name "/P0.5") (class "Default")
      (node (ref "RN3") (pin "6") (pinfunction "6_6") (pintype "unspecified"))
      (node (ref "U1") (pin "34") (pinfunction "P0.5_34") (pintype "unspecified"))
      (node (ref "U34") (pin "7") (pinfunction "A5_7") (pintype "unspecified"))
    )
    (net (code "25") (name "/P0.6") (class "Default")
      (node (ref "RN3") (pin "7") (pinfunction "7_7") (pintype "unspecified"))
      (node (ref "U1") (pin "33") (pinfunction "P0.6_33") (pintype "unspecified"))
      (node (ref "U34") (pin "8") (pinfunction "A6_8") (pintype "unspecified"))
    )
    (net (code "26") (name "/P0.7") (class "Default")
      (node (ref "RN3") (pin "8") (pinfunction "8_8") (pintype "unspecified"))
      (node (ref "U1") (pin "32") (pinfunction "P0.7_32") (pintype "unspecified"))
      (node (ref "U34") (pin "9") (pinfunction "A7_9") (pintype "unspecified"))
    )
    (net (code "27") (name "/P1.0") (class "Default")
      (node (ref "RN1") (pin "16") (pinfunction "16_16") (pintype "unspecified"))
      (node (ref "U1") (pin "1") (pinfunction "T2/P1.0_1") (pintype "unspecified"))
      (node (ref "U15") (pin "1") (pinfunction "1_1") (pintype "unspecified"))
      (node (ref "U15") (pin "2") (pinfunction "2_2") (pintype "unspecified"))
      (node (ref "U19") (pin "1") (pinfunction "1_1") (pintype "unspecified"))
      (node (ref "U19") (pin "2") (pinfunction "2_2") (pintype "unspecified"))
      (node (ref "U23") (pin "1") (pinfunction "1_1") (pintype "unspecified"))
      (node (ref "U23") (pin "2") (pinfunction "2_2") (pintype "unspecified"))
      (node (ref "U27") (pin "1") (pinfunction "1_1") (pintype "unspecified"))
      (node (ref "U27") (pin "2") (pinfunction "2_2") (pintype "unspecified"))
    )
    (net (code "28") (name "/P1.1") (class "Default")
      (node (ref "RN1") (pin "15") (pinfunction "15_15") (pintype "unspecified"))
      (node (ref "U1") (pin "2") (pinfunction "T2EX/P1.1_2") (pintype "unspecified"))
      (node (ref "U14") (pin "1") (pinfunction "1_1") (pintype "unspecified"))
      (node (ref "U14") (pin "2") (pinfunction "2_2") (pintype "unspecified"))
      (node (ref "U18") (pin "1") (pinfunction "1_1") (pintype "unspecified"))
      (node (ref "U18") (pin "2") (pinfunction "2_2") (pintype "unspecified"))
      (node (ref "U22") (pin "1") (pinfunction "1_1") (pintype "unspecified"))
      (node (ref "U22") (pin "2") (pinfunction "2_2") (pintype "unspecified"))
      (node (ref "U26") (pin "1") (pinfunction "1_1") (pintype "unspecified"))
      (node (ref "U26") (pin "2") (pinfunction "2_2") (pintype "unspecified"))
    )
    (net (code "29") (name "/P1.2") (class "Default")
      (node (ref "RN1") (pin "14") (pinfunction "14_14") (pintype "unspecified"))
      (node (ref "U1") (pin "3") (pinfunction "P1.2_3") (pintype "unspecified"))
      (node (ref "U13") (pin "1") (pinfunction "1_1") (pintype "unspecified"))
      (node (ref "U13") (pin "2") (pinfunction "2_2") (pintype "unspecified"))
      (node (ref "U17") (pin "1") (pinfunction "1_1") (pintype "unspecified"))
      (node (ref "U17") (pin "2") (pinfunction "2_2") (pintype "unspecified"))
      (node (ref "U21") (pin "1") (pinfunction "1_1") (pintype "unspecified"))
      (node (ref "U21") (pin "2") (pinfunction "2_2") (pintype "unspecified"))
      (node (ref "U25") (pin "1") (pinfunction "1_1") (pintype "unspecified"))
      (node (ref "U25") (pin "2") (pinfunction "2_2") (pintype "unspecified"))
    )
    (net (code "30") (name "/P1.3") (class "Default")
      (node (ref "RN1") (pin "13") (pinfunction "13_13") (pintype "unspecified"))
      (node (ref "U1") (pin "4") (pinfunction "P1.3_4") (pintype "unspecified"))
      (node (ref "U12") (pin "1") (pinfunction "1_1") (pintype "unspecified"))
      (node (ref "U12") (pin "2") (pinfunction "2_2") (pintype "unspecified"))
      (node (ref "U16") (pin "1") (pinfunction "1_1") (pintype "unspecified"))
      (node (ref "U16") (pin "2") (pinfunction "2_2") (pintype "unspecified"))
      (node (ref "U20") (pin "1") (pinfunction "1_1") (pintype "unspecified"))
      (node (ref "U20") (pin "2") (pinfunction "2_2") (pintype "unspecified"))
      (node (ref "U24") (pin "1") (pinfunction "1_1") (pintype "unspecified"))
      (node (ref "U24") (pin "2") (pinfunction "2_2") (pintype "unspecified"))
    )
    (net (code "31") (name "/P1.4") (class "Default")
      (node (ref "RN1") (pin "12") (pinfunction "12_12") (pintype "unspecified"))
      (node (ref "U1") (pin "5") (pinfunction "P1.4_5") (pintype "unspecified"))
      (node (ref "U24") (pin "3") (pinfunction "3_3") (pintype "unspecified"))
      (node (ref "U24") (pin "4") (pinfunction "4_4") (pintype "unspecified"))
      (node (ref "U25") (pin "3") (pinfunction "3_3") (pintype "unspecified"))
      (node (ref "U25") (pin "4") (pinfunction "4_4") (pintype "unspecified"))
      (node (ref "U26") (pin "3") (pinfunction "3_3") (pintype "unspecified"))
      (node (ref "U26") (pin "4") (pinfunction "4_4") (pintype "unspecified"))
      (node (ref "U27") (pin "3") (pinfunction "3_3") (pintype "unspecified"))
      (node (ref "U27") (pin "4") (pinfunction "4_4") (pintype "unspecified"))
    )
    (net (code "32") (name "/P1.5") (class "Default")
      (node (ref "RN1") (pin "11") (pinfunction "11_11") (pintype "unspecified"))
      (node (ref "U1") (pin "6") (pinfunction "P1.5_6") (pintype "unspecified"))
      (node (ref "U20") (pin "3") (pinfunction "3_3") (pintype "unspecified"))
      (node (ref "U20") (pin "4") (pinfunction "4_4") (pintype "unspecified"))
      (node (ref "U21") (pin "3") (pinfunction "3_3") (pintype "unspecified"))
      (node (ref "U21") (pin "4") (pinfunction "4_4") (pintype "unspecified"))
      (node (ref "U22") (pin "3") (pinfunction "3_3") (pintype "unspecified"))
      (node (ref "U22") (pin "4") (pinfunction "4_4") (pintype "unspecified"))
      (node (ref "U23") (pin "3") (pinfunction "3_3") (pintype "unspecified"))
      (node (ref "U23") (pin "4") (pinfunction "4_4") (pintype "unspecified"))
    )
    (net (code "33") (name "/P1.6") (class "Default")
      (node (ref "RN1") (pin "10") (pinfunction "10_10") (pintype "unspecified"))
      (node (ref "U1") (pin "7") (pinfunction "P1.6_7") (pintype "unspecified"))
      (node (ref "U16") (pin "3") (pinfunction "3_3") (pintype "unspecified"))
      (node (ref "U16") (pin "4") (pinfunction "4_4") (pintype "unspecified"))
      (node (ref "U17") (pin "3") (pinfunction "3_3") (pintype "unspecified"))
      (node (ref "U17") (pin "4") (pinfunction "4_4") (pintype "unspecified"))
      (node (ref "U18") (pin "3") (pinfunction "3_3") (pintype "unspecified"))
      (node (ref "U18") (pin "4") (pinfunction "4_4") (pintype "unspecified"))
      (node (ref "U19") (pin "3") (pinfunction "3_3") (pintype "unspecified"))
      (node (ref "U19") (pin "4") (pinfunction "4_4") (pintype "unspecified"))
    )
    (net (code "34") (name "/P1.7") (class "Default")
      (node (ref "RN1") (pin "9") (pinfunction "9_9") (pintype "unspecified"))
      (node (ref "U1") (pin "8") (pinfunction "P1.7_8") (pintype "unspecified"))
      (node (ref "U12") (pin "3") (pinfunction "3_3") (pintype "unspecified"))
      (node (ref "U12") (pin "4") (pinfunction "4_4") (pintype "unspecified"))
      (node (ref "U13") (pin "3") (pinfunction "3_3") (pintype "unspecified"))
      (node (ref "U13") (pin "4") (pinfunction "4_4") (pintype "unspecified"))
      (node (ref "U14") (pin "3") (pinfunction "3_3") (pintype "unspecified"))
      (node (ref "U14") (pin "4") (pinfunction "4_4") (pintype "unspecified"))
      (node (ref "U15") (pin "3") (pinfunction "3_3") (pintype "unspecified"))
      (node (ref "U15") (pin "4") (pinfunction "4_4") (pintype "unspecified"))
    )
    (net (code "35") (name "/P2.0") (class "Default")
      (node (ref "R15") (pin "1") (pinfunction "1_1") (pintype "unspecified"))
      (node (ref "RN4") (pin "8") (pinfunction "8_8") (pintype "unspecified"))
      (node (ref "U1") (pin "21") (pinfunction "P2.0_21") (pintype "unspecified"))
      (node (ref "U11") (pin "5") (pinfunction "SDA_5") (pintype "unspecified"))
    )
    (net (code "36") (name "/P2.1") (class "Default")
      (node (ref "R14") (pin "1") (pinfunction "1_1") (pintype "unspecified"))
      (node (ref "R20") (pin "1") (pinfunction "1_1") (pintype "unspecified"))
      (node (ref "RN4") (pin "7") (pinfunction "7_7") (pintype "unspecified"))
      (node (ref "U1") (pin "22") (pinfunction "P2.1_22") (pintype "unspecified"))
      (node (ref "U11") (pin "6") (pinfunction "SCL_6") (pintype "unspecified"))
    )
    (net (code "37") (name "/P2.2") (class "Default")
      (node (ref "R13") (pin "1") (pinfunction "1_1") (pintype "unspecified"))
      (node (ref "RN4") (pin "6") (pinfunction "6_6") (pintype "unspecified"))
      (node (ref "U1") (pin "23") (pinfunction "P2.2_23") (pintype "unspecified"))
      (node (ref "U29") (pin "1") (pinfunction "A0_1") (pintype "unspecified"))
    )
    (net (code "38") (name "/P2.3") (class "Default")
      (node (ref "R12") (pin "1") (pinfunction "1_1") (pintype "unspecified"))
      (node (ref "RN4") (pin "5") (pinfunction "5_5") (pintype "unspecified"))
      (node (ref "U1") (pin "24") (pinfunction "P2.3_24") (pintype "unspecified"))
      (node (ref "U29") (pin "2") (pinfunction "A1_2") (pintype "unspecified"))
    )
    (net (code "39") (name "/P2.4") (class "Default")
      (node (ref "R11") (pin "1") (pinfunction "1_1") (pintype "unspecified"))
      (node (ref "RN4") (pin "4") (pinfunction "4_4") (pintype "unspecified"))
      (node (ref "U1") (pin "25") (pinfunction "P2.4_25") (pintype "unspecified"))
      (node (ref "U29") (pin "3") (pinfunction "A2_3") (pintype "unspecified"))
    )
    (net (code "40") (name "/P2.5") (class "Default")
      (node (ref "BUZ1") (pin "2") (pinfunction "-_2") (pintype "unspecified"))
      (node (ref "R10") (pin "1") (pinfunction "1_1") (pintype "unspecified"))
      (node (ref "RN4") (pin "3") (pinfunction "3_3") (pintype "unspecified"))
      (node (ref "U1") (pin "26") (pinfunction "P2.5_26") (pintype "unspecified"))
    )
    (net (code "41") (name "/P2.6") (class "Default")
      (node (ref "R9") (pin "1") (pinfunction "1_1") (pintype "unspecified"))
      (node (ref "RN4") (pin "2") (pinfunction "2_2") (pintype "unspecified"))
      (node (ref "U1") (pin "27") (pinfunction "P2.6_27") (pintype "unspecified"))
    )
    (net (code "42") (name "/P2.7") (class "Default")
      (node (ref "R8") (pin "1") (pinfunction "1_1") (pintype "unspecified"))
      (node (ref "RN4") (pin "1") (pinfunction "1_1") (pintype "unspecified"))
      (node (ref "U1") (pin "28") (pinfunction "P2.7_28") (pintype "unspecified"))
    )
    (net (code "43") (name "/P3.2") (class "Default")
      (node (ref "RN2") (pin "14") (pinfunction "14_14") (pintype "unspecified"))
      (node (ref "U1") (pin "12") (pinfunction "INT0#/P3.2_12") (pintype "unspecified"))
      (node (ref "U10") (pin "1") (pinfunction "OUT_1") (pintype "unspecified"))
    )
    (net (code "44") (name "/P3.3") (class "Default")
      (node (ref "RN2") (pin "13") (pinfunction "13_13") (pintype "unspecified"))
      (node (ref "U1") (pin "13") (pinfunction "INT1#/P3.3_13") (pintype "unspecified"))
    )
    (net (code "45") (name "/P3.4") (class "Default")
      (node (ref "RN2") (pin "12") (pinfunction "12_12") (pintype "unspecified"))
      (node (ref "SW3") (pin "1") (pinfunction "1_1") (pintype "unspecified"))
      (node (ref "SW3") (pin "2") (pinfunction "2_2") (pintype "unspecified"))
      (node (ref "U1") (pin "14") (pinfunction "T0/P3.4_14") (pintype "unspecified"))
      (node (ref "U28") (pin "14") (pinfunction "DIN_14") (pintype "unspecified"))
      (node (ref "U8") (pin "6") (pinfunction "I/O_6") (pintype "unspecified"))
    )
    (net (code "46") (name "/P3.5") (class "Default")
      (node (ref "RN2") (pin "11") (pinfunction "11_11") (pintype "unspecified"))
      (node (ref "SW4") (pin "1") (pinfunction "1_1") (pintype "unspecified"))
      (node (ref "SW4") (pin "2") (pinfunction "2_2") (pintype "unspecified"))
      (node (ref "U1") (pin "15") (pinfunction "T1/P3.5_15") (pintype "unspecified"))
      (node (ref "U28") (pin "15") (pinfunction "CS#_15") (pintype "unspecified"))
      (node (ref "U8") (pin "5") (pinfunction "CE_5") (pintype "unspecified"))
    )
    (net (code "47") (name "/P3.6") (class "Default")
      (node (ref "RN2") (pin "10") (pinfunction "10_10") (pintype "unspecified"))
      (node (ref "SW5") (pin "1") (pinfunction "1_1") (pintype "unspecified"))
      (node (ref "SW5") (pin "2") (pinfunction "2_2") (pintype "unspecified"))
      (node (ref "U1") (pin "16") (pinfunction "WR#/P3.6_16") (pintype "unspecified"))
      (node (ref "U28") (pin "16") (pinfunction "DCLK_16") (pintype "unspecified"))
      (node (ref "U8") (pin "7") (pinfunction "SCLK_7") (pintype "unspecified"))
    )
    (net (code "48") (name "/P3.7") (class "Default")
      (node (ref "RN2") (pin "9") (pinfunction "9_9") (pintype "unspecified"))
      (node (ref "SW6") (pin "1") (pinfunction "1_1") (pintype "unspecified"))
      (node (ref "SW6") (pin "2") (pinfunction "2_2") (pintype "unspecified"))
      (node (ref "U1") (pin "17") (pinfunction "RD#/P3.7_17") (pintype "unspecified"))
      (node (ref "U28") (pin "12") (pinfunction "DOUT_12") (pintype "unspecified"))
      (node (ref "U7") (pin "2") (pinfunction "DQ_2") (pintype "unspecified"))
    )
    (net (code "49") (name "/RST") (class "Default")
      (node (ref "C1") (pin "2") (pinfunction "2_2") (pintype "input"))
      (node (ref "R1") (pin "1") (pinfunction "1_1") (pintype "input"))
      (node (ref "SW1") (pin "3") (pinfunction "3_3") (pintype "unspecified"))
      (node (ref "SW1") (pin "4") (pinfunction "4_4") (pintype "unspecified"))
      (node (ref "U1") (pin "9") (pinfunction "RST_9") (pintype "unspecified"))
    )
    (net (code "50") (name "/RXD") (class "Default")
      (node (ref "U1") (pin "10") (pinfunction "RXD/P3.0_10") (pintype "unspecified"))
      (node (ref "U4") (pin "2") (pinfunction "TXD_2") (pintype "unspecified"))
    )
    (net (code "51") (name "/TXD") (class "Default")
      (node (ref "U1") (pin "11") (pinfunction "TXD/P3.1_11") (pintype "unspecified"))
      (node (ref "U4") (pin "3") (pinfunction "RXD_3") (pintype "unspecified"))
    )
    (net (code "52") (name "/XTAL1") (class "Default")
      (node (ref "U1") (pin "18") (pinfunction "XTAL2_18") (pintype "unspecified"))
      (node (ref "U2") (pin "2") (pinfunction "2_2") (pintype "unspecified"))
      (node (ref "X1") (pin "1") (pinfunction "OSC1_1") (pintype "input"))
    )
    (net (code "53") (name "/XTAL2") (class "Default")
      (node (ref "U1") (pin "19") (pinfunction "XTAL1_19") (pintype "unspecified"))
      (node (ref "U3") (pin "1") (pinfunction "1_1") (pintype "unspecified"))
      (node (ref "X1") (pin "2") (pinfunction "OSC2_2") (pintype "input"))
    )
    (net (code "54") (name "GND") (class "Default")
      (node (ref "C2") (pin "2") (pinfunction "2_2") (pintype "unspecified"))
      (node (ref "C3") (pin "2") (pinfunction "2_2") (pintype "unspecified"))
      (node (ref "C4") (pin "2") (pinfunction "2_2") (pintype "unspecified"))
      (node (ref "C5") (pin "2") (pinfunction "2_2") (pintype "input"))
      (node (ref "C6") (pin "1") (pinfunction "1_1") (pintype "unspecified"))
      (node (ref "C7") (pin "2") (pinfunction "2_2") (pintype "unspecified"))
      (node (ref "C8") (pin "2") (pinfunction "2_2") (pintype "unspecified"))
      (node (ref "LED9") (pin "1") (pinfunction "K_1") (pintype "unspecified"))
      (node (ref "P1") (pin "2") (pinfunction "2_2") (pintype "unspecified"))
      (node (ref "R1") (pin "2") (pinfunction "2_2") (pintype "input"))
      (node (ref "R17") (pin "1") (pinfunction "1_1") (pintype "input"))
      (node (ref "R18") (pin "1") (pinfunction "1_1") (pintype "unspecified"))
      (node (ref "R19") (pin "1") (pinfunction "1_1") (pintype "unspecified"))
      (node (ref "R22") (pin "1") (pinfunction "1_1") (pintype "unspecified"))
      (node (ref "R25") (pin "1") (pinfunction "1_1") (pintype "unspecified"))
      (node (ref "R5") (pin "2") (pinfunction "2_2") (pintype "unspecified"))
      (node (ref "R6") (pin "2") (pinfunction "2_2") (pintype "unspecified"))
      (node (ref "SW3") (pin "3") (pinfunction "3_3") (pintype "unspecified"))
      (node (ref "SW3") (pin "4") (pinfunction "4_4") (pintype "unspecified"))
      (node (ref "SW4") (pin "3") (pinfunction "3_3") (pintype "unspecified"))
      (node (ref "SW4") (pin "4") (pinfunction "4_4") (pintype "unspecified"))
      (node (ref "SW5") (pin "3") (pinfunction "3_3") (pintype "unspecified"))
      (node (ref "SW5") (pin "4") (pinfunction "4_4") (pintype "unspecified"))
      (node (ref "SW6") (pin "3") (pinfunction "3_3") (pintype "unspecified"))
      (node (ref "SW6") (pin "4") (pinfunction "4_4") (pintype "unspecified"))
      (node (ref "U1") (pin "20") (pinfunction "GND_20") (pintype "unspecified"))
      (node (ref "U10") (pin "2") (pinfunction "GND_2") (pintype "unspecified"))
      (node (ref "U11") (pin "1") (pinfunction "A0_1") (pintype "unspecified"))
      (node (ref "U11") (pin "2") (pinfunction "A1_2") (pintype "unspecified"))
      (node (ref "U11") (pin "3") (pinfunction "A2_3") (pintype "unspecified"))
      (node (ref "U11") (pin "4") (pinfunction "GND_4") (pintype "unspecified"))
      (node (ref "U11") (pin "7") (pinfunction "WP_7") (pintype "unspecified"))
      (node (ref "U2") (pin "1") (pinfunction "1_1") (pintype "unspecified"))
      (node (ref "U28") (pin "4") (pinfunction "XN_4") (pintype "unspecified"))
      (node (ref "U28") (pin "5") (pinfunction "YN_5") (pintype "unspecified"))
      (node (ref "U28") (pin "6") (pinfunction "GND_6") (pintype "unspecified"))
      (node (ref "U29") (pin "4") (pinfunction "E1#_4") (pintype "unspecified"))
      (node (ref "U29") (pin "5") (pinfunction "E2#_5") (pintype "unspecified"))
      (node (ref "U29") (pin "8") (pinfunction "GND_8") (pintype "unspecified"))
      (node (ref "U3") (pin "2") (pinfunction "2_2") (pintype "unspecified"))
      (node (ref "U32") (pin "1") (pinfunction "1_1") (pintype "unspecified"))
      (node (ref "U33") (pin "4") (pinfunction "GND_4") (pintype "unspecified"))
      (node (ref "U34") (pin "10") (pinfunction "GND_10") (pintype "unspecified"))
      (node (ref "U34") (pin "19") (pinfunction "OE#_19") (pintype "unspecified"))
      (node (ref "U4") (pin "1") (pinfunction "GND_1") (pintype "unspecified"))
      (node (ref "U5") (pin "1") (pinfunction "ADJ(GND)_1") (pintype "unspecified"))
      (node (ref "U6") (pin "1") (pinfunction "1_1") (pintype "unspecified"))
      (node (ref "U7") (pin "1") (pinfunction "GND_1") (pintype "unspecified"))
      (node (ref "U8") (pin "4") (pinfunction "GND_4") (pintype "unspecified"))
      (node (ref "USB1") (pin "1") (pinfunction "GND_1") (pintype "unspecified"))
      (node (ref "USB1") (pin "12") (pinfunction "GND_12") (pintype "unspecified"))
      (node (ref "USB1") (pin "13") (pinfunction "SHELL_13") (pintype "unspecified"))
      (node (ref "USB1") (pin "14") (pinfunction "SHELL_14") (pintype "unspecified"))
    )
    (net (code "55") (name "Net-(BUZ1-+)") (class "Default")
      (node (ref "BUZ1") (pin "1") (pinfunction "+_1") (pintype "unspecified"))
      (node (ref "R7") (pin "1") (pinfunction "1_1") (pintype "unspecified"))
    )
    (net (code "56") (name "Net-(D1-A)") (class "Default")
      (node (ref "D1") (pin "11") (pinfunction "A_11") (pintype "input"))
      (node (ref "D2") (pin "11") (pinfunction "A_11") (pintype "input"))
      (node (ref "RN5") (pin "8") (pinfunction "8_8") (pintype "input"))
    )
    (net (code "57") (name "Net-(D1-B)") (class "Default")
      (node (ref "D1") (pin "7") (pinfunction "B_7") (pintype "input"))
      (node (ref "D2") (pin "7") (pinfunction "B_7") (pintype "input"))
      (node (ref "RN5") (pin "7") (pinfunction "7_7") (pintype "input"))
    )
    (net (code "58") (name "Net-(D1-C)") (class "Default")
      (node (ref "D1") (pin "4") (pinfunction "C_4") (pintype "input"))
      (node (ref "D2") (pin "4") (pinfunction "C_4") (pintype "input"))
      (node (ref "RN5") (pin "6") (pinfunction "6_6") (pintype "input"))
    )
    (net (code "59") (name "Net-(D1-D)") (class "Default")
      (node (ref "D1") (pin "2") (pinfunction "D_2") (pintype "input"))
      (node (ref "D2") (pin "2") (pinfunction "D_2") (pintype "input"))
      (node (ref "RN5") (pin "5") (pinfunction "5_5") (pintype "input"))
    )
    (net (code "60") (name "Net-(D1-DP)") (class "Default")
      (node (ref "D1") (pin "3") (pinfunction "DP_3") (pintype "input"))
      (node (ref "D2") (pin "3") (pinfunction "DP_3") (pintype "input"))
      (node (ref "RN6") (pin "5") (pinfunction "5_5") (pintype "input"))
    )
    (net (code "61") (name "Net-(D1-E)") (class "Default")
      (node (ref "D1") (pin "1") (pinfunction "E_1") (pintype "input"))
      (node (ref "D2") (pin "1") (pinfunction "E_1") (pintype "input"))
      (node (ref "RN6") (pin "8") (pinfunction "8_8") (pintype "input"))
    )
    (net (code "62") (name "Net-(D1-F)") (class "Default")
      (node (ref "D1") (pin "10") (pinfunction "F_10") (pintype "input"))
      (node (ref "D2") (pin "10") (pinfunction "F_10") (pintype "input"))
      (node (ref "RN6") (pin "7") (pinfunction "7_7") (pintype "input"))
    )
    (net (code "63") (name "Net-(D1-G)") (class "Default")
      (node (ref "D1") (pin "5") (pinfunction "G_5") (pintype "input"))
      (node (ref "D2") (pin "5") (pinfunction "G_5") (pintype "input"))
      (node (ref "RN6") (pin "6") (pinfunction "6_6") (pintype "input"))
    )
    (net (code "64") (name "Net-(LED1--)") (class "Default")
      (node (ref "LED1") (pin "1") (pinfunction "-_1") (pintype "unspecified"))
      (node (ref "R8") (pin "2") (pinfunction "2_2") (pintype "unspecified"))
    )
    (net (code "65") (name "Net-(LED2--)") (class "Default")
      (node (ref "LED2") (pin "1") (pinfunction "-_1") (pintype "unspecified"))
      (node (ref "R9") (pin "2") (pinfunction "2_2") (pintype "unspecified"))
    )
    (net (code "66") (name "Net-(LED3--)") (class "Default")
      (node (ref "LED3") (pin "1") (pinfunction "-_1") (pintype "unspecified"))
      (node (ref "R10") (pin "2") (pinfunction "2_2") (pintype "unspecified"))
    )
    (net (code "67") (name "Net-(LED4--)") (class "Default")
      (node (ref "LED4") (pin "1") (pinfunction "-_1") (pintype "unspecified"))
      (node (ref "R11") (pin "2") (pinfunction "2_2") (pintype "unspecified"))
    )
    (net (code "68") (name "Net-(LED5--)") (class "Default")
      (node (ref "LED5") (pin "1") (pinfunction "-_1") (pintype "unspecified"))
      (node (ref "R12") (pin "2") (pinfunction "2_2") (pintype "unspecified"))
    )
    (net (code "69") (name "Net-(LED6--)") (class "Default")
      (node (ref "LED6") (pin "1") (pinfunction "-_1") (pintype "unspecified"))
      (node (ref "R13") (pin "2") (pinfunction "2_2") (pintype "unspecified"))
    )
    (net (code "70") (name "Net-(LED7--)") (class "Default")
      (node (ref "LED7") (pin "1") (pinfunction "-_1") (pintype "unspecified"))
      (node (ref "R14") (pin "2") (pinfunction "2_2") (pintype "unspecified"))
    )
    (net (code "71") (name "Net-(LED8--)") (class "Default")
      (node (ref "LED8") (pin "1") (pinfunction "-_1") (pintype "unspecified"))
      (node (ref "R15") (pin "2") (pinfunction "2_2") (pintype "unspecified"))
    )
    (net (code "72") (name "Net-(LED9-A)") (class "Default")
      (node (ref "LED9") (pin "2") (pinfunction "A_2") (pintype "unspecified"))
      (node (ref "R23") (pin "1") (pinfunction "1_1") (pintype "unspecified"))
    )
    (net (code "73") (name "Net-(U1-EA#)") (class "Default")
      (node (ref "R2") (pin "1") (pinfunction "1_1") (pintype "unspecified"))
      (node (ref "U1") (pin "31") (pinfunction "EA#_31") (pintype "unspecified"))
    )
    (net (code "74") (name "Net-(U4-UD+)") (class "Default")
      (node (ref "R3") (pin "2") (pinfunction "2_2") (pintype "unspecified"))
      (node (ref "U4") (pin "5") (pinfunction "UD+_5") (pintype "unspecified"))
    )
    (net (code "75") (name "Net-(U4-UD-)") (class "Default")
      (node (ref "R4") (pin "2") (pinfunction "2_2") (pintype "unspecified"))
      (node (ref "U4") (pin "6") (pinfunction "UD-_6") (pintype "unspecified"))
    )
    (net (code "76") (name "Net-(U4-V3)") (class "Default")
      (node (ref "C4") (pin "1") (pinfunction "1_1") (pintype "unspecified"))
      (node (ref "U4") (pin "4") (pinfunction "V3_4") (pintype "unspecified"))
    )
    (net (code "77") (name "Net-(U4-VCC)") (class "Default")
      (node (ref "C3") (pin "1") (pinfunction "1_1") (pintype "unspecified"))
      (node (ref "C5") (pin "1") (pinfunction "1_1") (pintype "input"))
      (node (ref "C6") (pin "2") (pinfunction "2_2") (pintype "unspecified"))
      (node (ref "U4") (pin "16") (pinfunction "VCC_16") (pintype "unspecified"))
    )
    (net (code "78") (name "Net-(U8-X1)") (class "Default")
      (node (ref "C7") (pin "1") (pinfunction "1_1") (pintype "unspecified"))
      (node (ref "U8") (pin "2") (pinfunction "X1_2") (pintype "unspecified"))
      (node (ref "X2") (pin "2") (pinfunction "OSC2_2") (pintype "unspecified"))
    )
    (net (code "79") (name "Net-(U8-X2)") (class "Default")
      (node (ref "C8") (pin "1") (pinfunction "1_1") (pintype "unspecified"))
      (node (ref "U8") (pin "3") (pinfunction "X2_3") (pintype "unspecified"))
      (node (ref "X2") (pin "1") (pinfunction "OSC1_1") (pintype "unspecified"))
    )
    (net (code "80") (name "Net-(U33A-IN1+)") (class "Default")
      (node (ref "R20") (pin "2") (pinfunction "2_2") (pintype "unspecified"))
      (node (ref "U32") (pin "2") (pinfunction "2_2") (pintype "unspecified"))
      (node (ref "U33") (pin "3") (pinfunction "IN1+_3") (pintype "unspecified"))
    )
    (net (code "81") (name "Net-(U33A-IN1-)") (class "Default")
      (node (ref "R19") (pin "2") (pinfunction "2_2") (pintype "unspecified"))
      (node (ref "R21") (pin "1") (pinfunction "1_1") (pintype "unspecified"))
      (node (ref "U31") (pin "1") (pinfunction "1_1") (pintype "unspecified"))
      (node (ref "U33") (pin "2") (pinfunction "IN1-_2") (pintype "unspecified"))
    )
    (net (code "82") (name "Net-(U33A-OUT1)") (class "Default")
      (node (ref "R21") (pin "2") (pinfunction "2_2") (pintype "unspecified"))
      (node (ref "R24") (pin "1") (pinfunction "1_1") (pintype "unspecified"))
      (node (ref "U31") (pin "2") (pinfunction "2_2") (pintype "unspecified"))
      (node (ref "U33") (pin "1") (pinfunction "OUT1_1") (pintype "output"))
    )
    (net (code "83") (name "Net-(U34-B0)") (class "Default")
      (node (ref "RN5") (pin "1") (pinfunction "1_1") (pintype "input"))
      (node (ref "U34") (pin "18") (pinfunction "B0_18") (pintype "unspecified"))
    )
    (net (code "84") (name "Net-(U34-B1)") (class "Default")
      (node (ref "RN5") (pin "2") (pinfunction "2_2") (pintype "input"))
      (node (ref "U34") (pin "17") (pinfunction "B1_17") (pintype "unspecified"))
    )
    (net (code "85") (name "Net-(U34-B2)") (class "Default")
      (node (ref "RN5") (pin "3") (pinfunction "3_3") (pintype "input"))
      (node (ref "U34") (pin "16") (pinfunction "B2_16") (pintype "unspecified"))
    )
    (net (code "86") (name "Net-(U34-B3)") (class "Default")
      (node (ref "RN5") (pin "4") (pinfunction "4_4") (pintype "input"))
      (node (ref "U34") (pin "15") (pinfunction "B3_15") (pintype "unspecified"))
    )
    (net (code "87") (name "Net-(U34-B4)") (class "Default")
      (node (ref "RN6") (pin "1") (pinfunction "1_1") (pintype "input"))
      (node (ref "U34") (pin "14") (pinfunction "B4_14") (pintype "unspecified"))
    )
    (net (code "88") (name "Net-(U34-B5)") (class "Default")
      (node (ref "RN6") (pin "2") (pinfunction "2_2") (pintype "input"))
      (node (ref "U34") (pin "13") (pinfunction "B5_13") (pintype "unspecified"))
    )
    (net (code "89") (name "Net-(U34-B6)") (class "Default")
      (node (ref "RN6") (pin "3") (pinfunction "3_3") (pintype "input"))
      (node (ref "U34") (pin "12") (pinfunction "B6_12") (pintype "unspecified"))
    )
    (net (code "90") (name "Net-(U34-B7)") (class "Default")
      (node (ref "RN6") (pin "4") (pinfunction "4_4") (pintype "input"))
      (node (ref "U34") (pin "11") (pinfunction "B7_11") (pintype "unspecified"))
    )
    (net (code "91") (name "Net-(USB1-CC1)") (class "Default")
      (node (ref "R5") (pin "1") (pinfunction "1_1") (pintype "unspecified"))
      (node (ref "USB1") (pin "4") (pinfunction "CC1_4") (pintype "unspecified"))
    )
    (net (code "92") (name "Net-(USB1-CC2)") (class "Default")
      (node (ref "R6") (pin "1") (pinfunction "1_1") (pintype "unspecified"))
      (node (ref "USB1") (pin "10") (pinfunction "CC2_10") (pintype "unspecified"))
    )
    (net (code "93") (name "VCC") (class "Default")
      (node (ref "C1") (pin "1") (pinfunction "1_1") (pintype "input"))
      (node (ref "C2") (pin "1") (pinfunction "1_1") (pintype "unspecified"))
      (node (ref "LED1") (pin "2") (pinfunction "+_2") (pintype "unspecified"))
      (node (ref "LED2") (pin "2") (pinfunction "+_2") (pintype "unspecified"))
      (node (ref "LED3") (pin "2") (pinfunction "+_2") (pintype "unspecified"))
      (node (ref "LED4") (pin "2") (pinfunction "+_2") (pintype "unspecified"))
      (node (ref "LED5") (pin "2") (pinfunction "+_2") (pintype "unspecified"))
      (node (ref "LED6") (pin "2") (pinfunction "+_2") (pintype "unspecified"))
      (node (ref "LED7") (pin "2") (pinfunction "+_2") (pintype "unspecified"))
      (node (ref "LED8") (pin "2") (pinfunction "+_2") (pintype "unspecified"))
      (node (ref "R16") (pin "2") (pinfunction "2_2") (pintype "input"))
      (node (ref "R2") (pin "2") (pinfunction "2_2") (pintype "unspecified"))
      (node (ref "R25") (pin "3") (pinfunction "3_3") (pintype "unspecified"))
      (node (ref "R7") (pin "2") (pinfunction "2_2") (pintype "unspecified"))
      (node (ref "RN1") (pin "1") (pinfunction "1_1") (pintype "unspecified"))
      (node (ref "RN1") (pin "2") (pinfunction "2_2") (pintype "unspecified"))
      (node (ref "RN1") (pin "3") (pinfunction "3_3") (pintype "unspecified"))
      (node (ref "RN1") (pin "4") (pinfunction "4_4") (pintype "unspecified"))
      (node (ref "RN1") (pin "5") (pinfunction "5_5") (pintype "unspecified"))
      (node (ref "RN1") (pin "6") (pinfunction "6_6") (pintype "unspecified"))
      (node (ref "RN1") (pin "7") (pinfunction "7_7") (pintype "unspecified"))
      (node (ref "RN1") (pin "8") (pinfunction "8_8") (pintype "unspecified"))
      (node (ref "RN2") (pin "1") (pinfunction "1_1") (pintype "unspecified"))
      (node (ref "RN2") (pin "2") (pinfunction "2_2") (pintype "unspecified"))
      (node (ref "RN2") (pin "3") (pinfunction "3_3") (pintype "unspecified"))
      (node (ref "RN2") (pin "4") (pinfunction "4_4") (pintype "unspecified"))
      (node (ref "RN2") (pin "5") (pinfunction "5_5") (pintype "unspecified"))
      (node (ref "RN2") (pin "6") (pinfunction "6_6") (pintype "unspecified"))
      (node (ref "RN2") (pin "7") (pinfunction "7_7") (pintype "unspecified"))
      (node (ref "RN2") (pin "8") (pinfunction "8_8") (pintype "unspecified"))
      (node (ref "RN3") (pin "10") (pinfunction "10_10") (pintype "unspecified"))
      (node (ref "RN3") (pin "11") (pinfunction "11_11") (pintype "unspecified"))
      (node (ref "RN3") (pin "12") (pinfunction "12_12") (pintype "unspecified"))
      (node (ref "RN3") (pin "13") (pinfunction "13_13") (pintype "unspecified"))
      (node (ref "RN3") (pin "14") (pinfunction "14_14") (pintype "unspecified"))
      (node (ref "RN3") (pin "15") (pinfunction "15_15") (pintype "unspecified"))
      (node (ref "RN3") (pin "16") (pinfunction "16_16") (pintype "unspecified"))
      (node (ref "RN3") (pin "9") (pinfunction "9_9") (pintype "unspecified"))
      (node (ref "RN4") (pin "10") (pinfunction "10_10") (pintype "unspecified"))
      (node (ref "RN4") (pin "11") (pinfunction "11_11") (pintype "unspecified"))
      (node (ref "RN4") (pin "12") (pinfunction "12_12") (pintype "unspecified"))
      (node (ref "RN4") (pin "13") (pinfunction "13_13") (pintype "unspecified"))
      (node (ref "RN4") (pin "14") (pinfunction "14_14") (pintype "unspecified"))
      (node (ref "RN4") (pin "15") (pinfunction "15_15") (pintype "unspecified"))
      (node (ref "RN4") (pin "16") (pinfunction "16_16") (pintype "unspecified"))
      (node (ref "RN4") (pin "9") (pinfunction "9_9") (pintype "unspecified"))
      (node (ref "SW1") (pin "1") (pinfunction "1_1") (pintype "unspecified"))
      (node (ref "SW1") (pin "2") (pinfunction "2_2") (pintype "unspecified"))
      (node (ref "SW2") (pin "2") (pinfunction "2_2") (pintype "unspecified"))
      (node (ref "SW2") (pin "3") (pinfunction "3_3") (pintype "unspecified"))
      (node (ref "SW2") (pin "5") (pinfunction "5_5") (pintype "unspecified"))
      (node (ref "SW2") (pin "6") (pinfunction "6_6") (pintype "unspecified"))
      (node (ref "U1") (pin "40") (pinfunction "VCC_40") (pintype "unspecified"))
      (node (ref "U10") (pin "3") (pinfunction "VCC_3") (pintype "unspecified"))
      (node (ref "U11") (pin "8") (pinfunction "VCC_8") (pintype "unspecified"))
      (node (ref "U28") (pin "1") (pinfunction "VCC_1") (pintype "unspecified"))
      (node (ref "U28") (pin "10") (pinfunction "IOVDD_10") (pintype "unspecified"))
      (node (ref "U28") (pin "9") (pinfunction "VREF_9") (pintype "unspecified"))
      (node (ref "U29") (pin "16") (pinfunction "VCC_16") (pintype "unspecified"))
      (node (ref "U29") (pin "6") (pinfunction "E3_6") (pintype "unspecified"))
      (node (ref "U30") (pin "1") (pinfunction "1_1") (pintype "unspecified"))
      (node (ref "U33") (pin "8") (pinfunction "VCC_8") (pintype "unspecified"))
      (node (ref "U34") (pin "1") (pinfunction "DIR_1") (pintype "unspecified"))
      (node (ref "U34") (pin "20") (pinfunction "VCC_20") (pintype "unspecified"))
      (node (ref "U7") (pin "3") (pinfunction "VDD_3") (pintype "unspecified"))
      (node (ref "U8") (pin "1") (pinfunction "VCC2_1") (pintype "unspecified"))
    )
    (net (code "94") (name "unconnected-(RN2-Pad15)") (class "Default")
      (node (ref "RN2") (pin "15") (pinfunction "15_15") (pintype "unspecified+no_connect"))
    )
    (net (code "95") (name "unconnected-(RN2-Pad16)") (class "Default")
      (node (ref "RN2") (pin "16") (pinfunction "16_16") (pintype "unspecified+no_connect"))
    )
    (net (code "96") (name "unconnected-(U1-ALE-Pad30)") (class "Default")
      (node (ref "U1") (pin "30") (pinfunction "ALE_30") (pintype "unspecified+no_connect"))
    )
    (net (code "97") (name "unconnected-(U1-PSEN#-Pad29)") (class "Default")
      (node (ref "U1") (pin "29") (pinfunction "PSEN#_29") (pintype "unspecified+no_connect"))
    )
    (net (code "98") (name "unconnected-(U4-CTS#-Pad9)") (class "Default")
      (node (ref "U4") (pin "9") (pinfunction "CTS#_9") (pintype "unspecified+no_connect"))
    )
    (net (code "99") (name "unconnected-(U4-DCD#-Pad12)") (class "Default")
      (node (ref "U4") (pin "12") (pinfunction "DCD#_12") (pintype "unspecified+no_connect"))
    )
    (net (code "100") (name "unconnected-(U4-DSR#-Pad10)") (class "Default")
      (node (ref "U4") (pin "10") (pinfunction "DSR#_10") (pintype "unspecified+no_connect"))
    )
    (net (code "101") (name "unconnected-(U4-DTR#-Pad13)") (class "Default")
      (node (ref "U4") (pin "13") (pinfunction "DTR#_13") (pintype "unspecified+no_connect"))
    )
    (net (code "102") (name "unconnected-(U4-R232-Pad15)") (class "Default")
      (node (ref "U4") (pin "15") (pinfunction "R232_15") (pintype "unspecified+no_connect"))
    )
    (net (code "103") (name "unconnected-(U4-RI#-Pad11)") (class "Default")
      (node (ref "U4") (pin "11") (pinfunction "RI#_11") (pintype "unspecified+no_connect"))
    )
    (net (code "104") (name "unconnected-(U4-RTS#-Pad14)") (class "Default")
      (node (ref "U4") (pin "14") (pinfunction "RTS#_14") (pintype "unspecified+no_connect"))
    )
    (net (code "105") (name "unconnected-(U4-XI-Pad7)") (class "Default")
      (node (ref "U4") (pin "7") (pinfunction "XI_7") (pintype "unspecified+no_connect"))
    )
    (net (code "106") (name "unconnected-(U4-XO-Pad8)") (class "Default")
      (node (ref "U4") (pin "8") (pinfunction "XO_8") (pintype "unspecified+no_connect"))
    )
    (net (code "107") (name "unconnected-(U8-VCC1-Pad8)") (class "Default")
      (node (ref "U8") (pin "8") (pinfunction "VCC1_8") (pintype "unspecified+no_connect"))
    )
    (net (code "108") (name "unconnected-(U28-BUSY-Pad13)") (class "Default")
      (node (ref "U28") (pin "13") (pinfunction "BUSY_13") (pintype "unspecified+no_connect"))
    )
    (net (code "109") (name "unconnected-(U28-PENIRQ#-Pad11)") (class "Default")
      (node (ref "U28") (pin "11") (pinfunction "PENIRQ#_11") (pintype "unspecified+no_connect"))
    )
    (net (code "110") (name "unconnected-(USB1-SBU1-Pad9)") (class "Default")
      (node (ref "USB1") (pin "9") (pinfunction "SBU1_9") (pintype "unspecified+no_connect"))
    )
    (net (code "111") (name "unconnected-(USB1-SBU2-Pad3)") (class "Default")
      (node (ref "USB1") (pin "3") (pinfunction "SBU2_3") (pintype "unspecified+no_connect"))
    )
  )
)
